# SWR_HF.net
KiCad netlist of a schematic drawn in Altium Designer
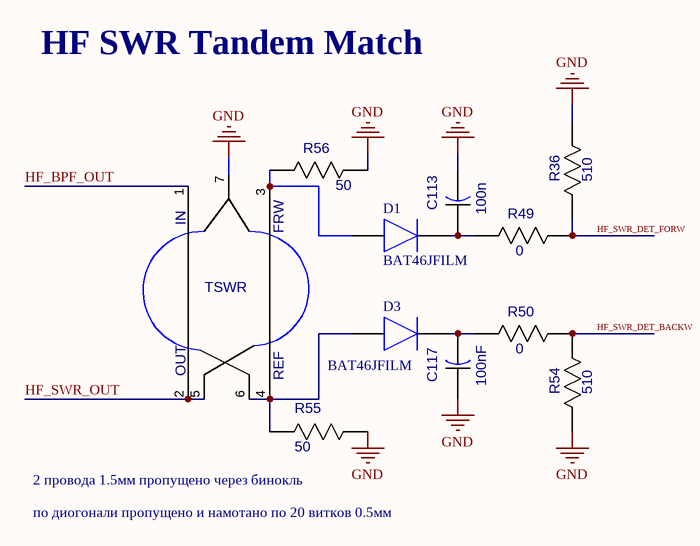
[diagram p0: SWR_HF.SchDoc]

(export (version "E")
  (design (tool "Eeschema 10.0.6"))
  (components
    (comp (ref "C113")
      (value "100n")
      (footprint "CAP_0805")
      (description "CAP_0805")
      (libsource (lib "*") (part "CAP_0805"))
    )
    (comp (ref "C117")
      (value "100nF")
      (footprint "CAP_0805")
      (description "CAP_0805")
      (libsource (lib "*") (part "CAP_0805"))
    )
    (comp (ref "D1")
      (value "BAT46JFILM")
      (footprint "SOD2513X117N")
      (description "Diode")
      (fields (field (name "MOUSER PART NUMBER") "511-BAT46JFILM") (field (name "RS PART NUMBER") "7146847P"))
      (libsource (lib "RF-UNIT-BIG_1") (part "BAT46JFILM"))
    )
    (comp (ref "D3")
      (value "BAT46JFILM")
      (footprint "SOD2513X117N")
      (description "Diode")
      (fields (field (name "MOUSER PART NUMBER") "511-BAT46JFILM") (field (name "RS PART NUMBER") "7146847P"))
      (libsource (lib "RF-UNIT-BIG_1") (part "BAT46JFILM"))
    )
    (comp (ref "R36")
      (value "510")
      (footprint "RES_0805")
      (description "RES_0805")
      (libsource (lib "*") (part "RES_0805"))
    )
    (comp (ref "R49")
      (value "0")
      (footprint "RES_0805")
      (description "RES_0805")
      (libsource (lib "*") (part "RES_0805"))
    )
    (comp (ref "R50")
      (value "0")
      (footprint "RES_0805")
      (description "RES_0805")
      (libsource (lib "*") (part "RES_0805"))
    )
    (comp (ref "R54")
      (value "510")
      (footprint "RES_0805")
      (description "RES_0805")
      (libsource (lib "*") (part "RES_0805"))
    )
    (comp (ref "R55")
      (value "50")
      (footprint "RES_1206")
      (description "RES_1206")
      (libsource (lib "*") (part "RES_1206"))
    )
    (comp (ref "R56")
      (value "50")
      (footprint "RES_1206")
      (description "RES_1206")
      (libsource (lib "*") (part "RES_1206"))
    )
    (comp (ref "TSWR")
      (value "SWR_TANDEM_MATCH")
      (footprint "SWR_TANDEM_MATCH")
      (libsource (lib "*") (part "SWR_TANDEM_MATCH"))
    )
  )
  (nets
    (net (code "1") (name "/HF_BPF_OUT") (class "Default")
      (node (ref "TSWR") (pin "1") (pinfunction "1_1") (pintype "passive"))
    )
    (net (code "2") (name "/HF_SWR_DET_BACKW") (class "Default")
      (node (ref "R50") (pin "2") (pinfunction "2_2") (pintype "passive"))
      (node (ref "R54") (pin "2") (pinfunction "2_2") (pintype "passive"))
    )
    (net (code "3") (name "/HF_SWR_DET_FORW") (class "Default")
      (node (ref "R36") (pin "1") (pinfunction "1_1") (pintype "passive"))
      (node (ref "R49") (pin "2") (pinfunction "2_2") (pintype "passive"))
    )
    (net (code "4") (name "/HF_SWR_OUT") (class "Default")
      (node (ref "TSWR") (pin "2") (pinfunction "2_2") (pintype "passive"))
      (node (ref "TSWR") (pin "5") (pinfunction "5_5") (pintype "passive"))
    )
    (net (code "5") (name "GND") (class "Default")
      (node (ref "C113") (pin "2") (pinfunction "2_2") (pintype "passive"))
      (node (ref "C117") (pin "1") (pinfunction "1_1") (pintype "passive"))
      (node (ref "R36") (pin "2") (pinfunction "2_2") (pintype "passive"))
      (node (ref "R54") (pin "1") (pinfunction "1_1") (pintype "passive"))
      (node (ref "R55") (pin "2") (pinfunction "2_2") (pintype "passive"))
      (node (ref "R56") (pin "2") (pinfunction "2_2") (pintype "passive"))
      (node (ref "TSWR") (pin "7") (pinfunction "7_7") (pintype "passive"))
    )
    (net (code "6") (name "Net-(D1-A)") (class "Default")
      (node (ref "D1") (pin "2") (pinfunction "A_2") (pintype "passive"))
      (node (ref "R56") (pin "1") (pinfunction "1_1") (pintype "passive"))
      (node (ref "TSWR") (pin "3") (pinfunction "3_3") (pintype "passive"))
    )
    (net (code "7") (name "Net-(D1-K)") (class "Default")
      (node (ref "C113") (pin "1") (pinfunction "1_1") (pintype "passive"))
      (node (ref "D1") (pin "1") (pinfunction "K_1") (pintype "passive"))
      (node (ref "R49") (pin "1") (pinfunction "1_1") (pintype "passive"))
    )
    (net (code "8") (name "Net-(D3-A)") (class "Default")
      (node (ref "D3") (pin "2") (pinfunction "A_2") (pintype "passive"))
      (node (ref "R55") (pin "1") (pinfunction "1_1") (pintype "passive"))
      (node (ref "TSWR") (pin "4") (pinfunction "4_4") (pintype "passive"))
      (node (ref "TSWR") (pin "6") (pinfunction "6_6") (pintype "passive"))
    )
    (net (code "9") (name "Net-(D3-K)") (class "Default")
      (node (ref "C117") (pin "2") (pinfunction "2_2") (pintype "passive"))
      (node (ref "D3") (pin "1") (pinfunction "K_1") (pintype "passive"))
      (node (ref "R50") (pin "1") (pinfunction "1_1") (pintype "passive"))
    )
  )
)
